# Connectors.net
KiCad netlist of a schematic drawn in Altium Designer
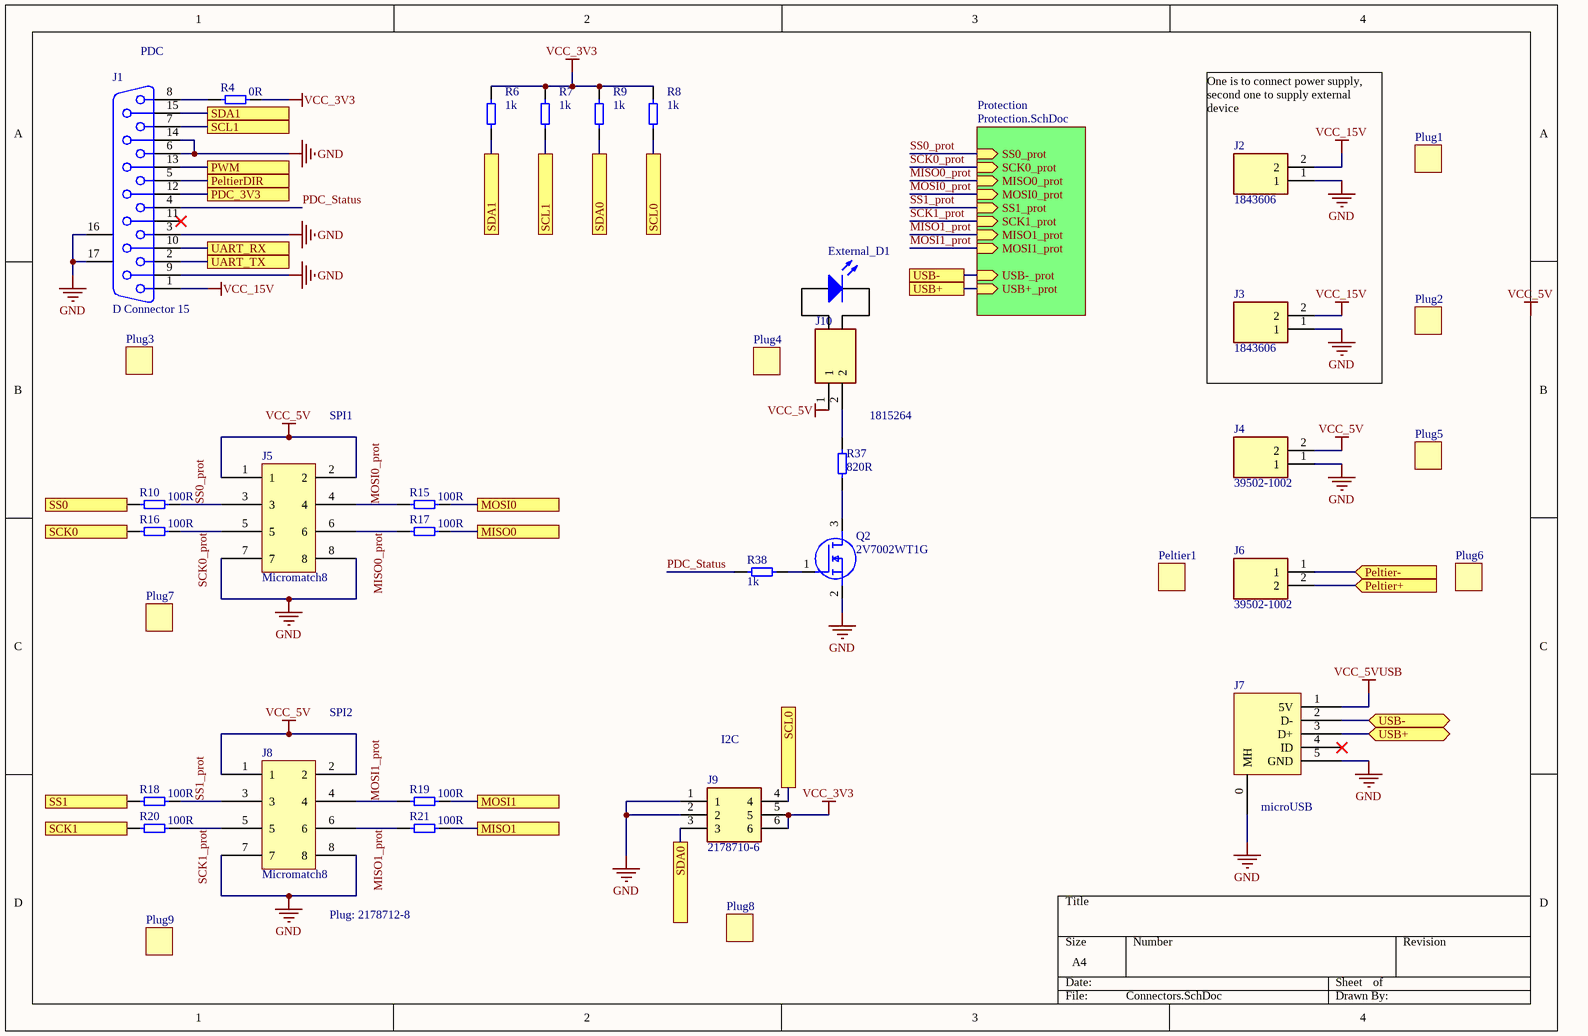
[diagram p0: Connectors.SchDoc]

(export (version "E")
  (design (tool "Eeschema 10.0.6"))
  (components
    (comp (ref "External_D1")
      (value "LED0")
      (description "External panel mounted LED")
      (fields (field (name "MANUFACTURER") "Dialight"))
      (libsource (lib "Miscellaneous Devices") (part "LED0"))
    )
    (comp (ref "J1")
      (value "D Connector 15")
      (footprint "DSUB_15_D15S33E4GV00LF")
      (description "Receptacle Assembly, 15 Position, Right Angle")
      (fields (field (name "MANUFACTURER") "Amphenol ICC") (field (name "PUBLISHER") "Altium Limited"))
      (libsource (lib "Miscellaneous Connectors") (part "D Connector 15"))
    )
    (comp (ref "J2")
      (value "1843606")
      (footprint "MouserDropbox:SHDR2W80P0X350_1X2_840X725X920P")
      (description "Connector")
      (fields (field (name "MOUSER PART NUMBER") "651-1843606") (field (name "RS PART NUMBER") "8042194"))
      (libsource (lib "*") (part "1843606"))
    )
    (comp (ref "J3")
      (value "1843606")
      (footprint "MouserDropbox:SHDR2W80P0X350_1X2_840X725X920P")
      (description "Connector")
      (fields (field (name "MOUSER PART NUMBER") "651-1843606") (field (name "RS PART NUMBER") "8042194"))
      (libsource (lib "*") (part "1843606"))
    )
    (comp (ref "J4")
      (value "39502-1002")
      (footprint "MouserDropbox:SHDR2W110P0X350_1X2_840X920X690P")
      (description "Connector")
      (fields (field (name "MOUSER PART NUMBER") "538-39502-1002"))
      (libsource (lib "*") (part "39502-1002"))
    )
    (comp (ref "J5")
      (value "Micromatch8")
      (footprint "micromatch8")
      (fields (field (name "MANUFACTURER") "TE Connectivity"))
      (libsource (lib "connectorsSymbols") (part "Micromatch8"))
    )
    (comp (ref "J6")
      (value "39502-1002")
      (footprint "MouserDropbox:SHDR2W110P0X350_1X2_840X920X690P")
      (description "Connector")
      (fields (field (name "MOUSER PART NUMBER") "538-39502-1002"))
      (libsource (lib "") (part "39502-1002_1"))
    )
    (comp (ref "J7")
      (value "microUSB")
      (footprint "microUSB_molex_476540001")
      (description "Molex 476540001")
      (fields (field (name "MANUFACTURER") "Molex"))
      (libsource (lib "connectorsSymbols") (part "microUSB_molex_476540001"))
    )
    (comp (ref "J8")
      (value "Micromatch8")
      (footprint "micromatch8")
      (fields (field (name "MANUFACTURER") "TE Connectivity"))
      (libsource (lib "connectorsSymbols") (part "Micromatch8"))
    )
    (comp (ref "J9")
      (value "2178710-6")
      (footprint "MouserDropbox:21787106")
      (description "Connector")
      (fields (field (name "MOUSER PART NUMBER") "571-2178710-6") (field (name "RS PART NUMBER") "8475468P"))
      (libsource (lib "*") (part "2178710-6"))
    )
    (comp (ref "J10")
      (value "1815264")
      (footprint "MouserDropbox:1815264")
      (description "Connector")
      (fields (field (name "MOUSER PART NUMBER") "651-1815264") (field (name "RS PART NUMBER") "8020138"))
      (libsource (lib "*") (part "1815264"))
    )
    (comp (ref "Peltier1")
      (value "plug")
      (fields (field (name "MANUFACTURER") "Laird Thermal Systems"))
      (libsource (lib "connectorsSymbols") (part "plug"))
    )
    (comp (ref "Plug1")
      (value "plug")
      (fields (field (name "MANUFACTURER") "Phoenix Contact"))
      (libsource (lib "connectorsSymbols") (part "plug"))
    )
    (comp (ref "Plug2")
      (value "plug")
      (fields (field (name "MANUFACTURER") "Phoenix Contact"))
      (libsource (lib "connectorsSymbols") (part "plug"))
    )
    (comp (ref "Plug3")
      (value "plug")
      (fields (field (name "MANUFACTURER") "Amphenol"))
      (libsource (lib "connectorsSymbols") (part "plug"))
    )
    (comp (ref "Plug4")
      (value "plug")
      (fields (field (name "MANUFACTURER") "Phoenix Contact"))
      (libsource (lib "connectorsSymbols") (part "plug"))
    )
    (comp (ref "Plug5")
      (value "plug")
      (fields (field (name "MANUFACTURER") "Molex"))
      (libsource (lib "connectorsSymbols") (part "plug"))
    )
    (comp (ref "Plug6")
      (value "plug")
      (fields (field (name "MANUFACTURER") "Molex"))
      (libsource (lib "connectorsSymbols") (part "plug"))
    )
    (comp (ref "Plug7")
      (value "plug")
      (fields (field (name "MANUFACTURER") "TE Connectivity"))
      (libsource (lib "connectorsSymbols") (part "plug"))
    )
    (comp (ref "Plug8")
      (value "plug")
      (fields (field (name "MANUFACTURER") "TE Connectivity"))
      (libsource (lib "connectorsSymbols") (part "plug"))
    )
    (comp (ref "Plug9")
      (value "plug")
      (fields (field (name "MANUFACTURER") "TE Connectivity"))
      (libsource (lib "connectorsSymbols") (part "plug"))
    )
    (comp (ref "Q2")
      (value "2V7002WT1G")
      (footprint "MouserDropbox:SOT65P220X100-3N")
      (description "MOSFET (N-Channel)")
      (fields (field (name "MOUSER PART NUMBER") "863-2V7002WT1G") (field (name "RS PART NUMBER") "7905246P"))
      (libsource (lib "*") (part "2V7002WT1G"))
    )
    (comp (ref "R4")
      (value "0R")
      (footprint "0603-Resistor")
      (description "Resistor")
      (fields (field (name "PART NUMBER") "R0603"))
      (libsource (lib "ZUIAM_LIB") (part "Resistor"))
    )
    (comp (ref "R6")
      (value "1k")
      (footprint "0603-Resistor")
      (description "Resistor")
      (fields (field (name "PART NUMBER") "R0603"))
      (libsource (lib "") (part "Resistor_1"))
    )
    (comp (ref "R7")
      (value "1k")
      (footprint "0603-Resistor")
      (description "Resistor")
      (fields (field (name "PART NUMBER") "R0603"))
      (libsource (lib "") (part "Resistor_1"))
    )
    (comp (ref "R8")
      (value "1k")
      (footprint "0603-Resistor")
      (description "Resistor")
      (fields (field (name "PART NUMBER") "R0603"))
      (libsource (lib "") (part "Resistor_1"))
    )
    (comp (ref "R9")
      (value "1k")
      (footprint "0603-Resistor")
      (description "Resistor")
      (fields (field (name "PART NUMBER") "R0603"))
      (libsource (lib "") (part "Resistor_1"))
    )
    (comp (ref "R10")
      (value "100R")
      (footprint "0603-Resistor")
      (description "Resistor")
      (fields (field (name "PART NUMBER") "R0603"))
      (libsource (lib "ZUIAM_LIB") (part "Resistor"))
    )
    (comp (ref "R15")
      (value "100R")
      (footprint "0603-Resistor")
      (description "Resistor")
      (fields (field (name "PART NUMBER") "R0603"))
      (libsource (lib "ZUIAM_LIB") (part "Resistor"))
    )
    (comp (ref "R16")
      (value "100R")
      (footprint "0603-Resistor")
      (description "Resistor")
      (fields (field (name "PART NUMBER") "R0603"))
      (libsource (lib "ZUIAM_LIB") (part "Resistor"))
    )
    (comp (ref "R17")
      (value "100R")
      (footprint "0603-Resistor")
      (description "Resistor")
      (fields (field (name "PART NUMBER") "R0603"))
      (libsource (lib "ZUIAM_LIB") (part "Resistor"))
    )
    (comp (ref "R18")
      (value "100R")
      (footprint "0603-Resistor")
      (description "Resistor")
      (fields (field (name "PART NUMBER") "R0603"))
      (libsource (lib "ZUIAM_LIB") (part "Resistor"))
    )
    (comp (ref "R19")
      (value "100R")
      (footprint "0603-Resistor")
      (description "Resistor")
      (fields (field (name "PART NUMBER") "R0603"))
      (libsource (lib "ZUIAM_LIB") (part "Resistor"))
    )
    (comp (ref "R20")
      (value "100R")
      (footprint "0603-Resistor")
      (description "Resistor")
      (fields (field (name "PART NUMBER") "R0603"))
      (libsource (lib "ZUIAM_LIB") (part "Resistor"))
    )
    (comp (ref "R21")
      (value "100R")
      (footprint "0603-Resistor")
      (description "Resistor")
      (fields (field (name "PART NUMBER") "R0603"))
      (libsource (lib "ZUIAM_LIB") (part "Resistor"))
    )
    (comp (ref "R37")
      (value "820R")
      (footprint "0603-Resistor")
      (description "Resistor")
      (fields (field (name "PART NUMBER") "R0603"))
      (libsource (lib "") (part "Resistor_2"))
    )
    (comp (ref "R38")
      (value "1k")
      (footprint "0603-Resistor")
      (description "Resistor")
      (fields (field (name "PART NUMBER") "R0603"))
      (libsource (lib "ZUIAM_LIB") (part "Resistor"))
    )
  )
  (nets
    (net (code "1") (name "/MISO0") (class "Default")
      (node (ref "R17") (pin "1") (pinfunction "1_1") (pintype "passive"))
    )
    (net (code "2") (name "/MISO0_prot") (class "Default")
      (node (ref "J5") (pin "6") (pinfunction "6_6") (pintype "passive"))
      (node (ref "R17") (pin "2") (pinfunction "2_2") (pintype "passive"))
    )
    (net (code "3") (name "/MISO1") (class "Default")
      (node (ref "R21") (pin "1") (pinfunction "1_1") (pintype "passive"))
    )
    (net (code "4") (name "/MISO1_prot") (class "Default")
      (node (ref "J8") (pin "6") (pinfunction "6_6") (pintype "passive"))
      (node (ref "R21") (pin "2") (pinfunction "2_2") (pintype "passive"))
    )
    (net (code "5") (name "/MOSI0") (class "Default")
      (node (ref "R15") (pin "1") (pinfunction "1_1") (pintype "passive"))
    )
    (net (code "6") (name "/MOSI0_prot") (class "Default")
      (node (ref "J5") (pin "4") (pinfunction "4_4") (pintype "passive"))
      (node (ref "R15") (pin "2") (pinfunction "2_2") (pintype "passive"))
    )
    (net (code "7") (name "/MOSI1") (class "Default")
      (node (ref "R19") (pin "1") (pinfunction "1_1") (pintype "passive"))
    )
    (net (code "8") (name "/MOSI1_prot") (class "Default")
      (node (ref "J8") (pin "4") (pinfunction "4_4") (pintype "passive"))
      (node (ref "R19") (pin "2") (pinfunction "2_2") (pintype "passive"))
    )
    (net (code "9") (name "/PDC_3V3") (class "Default")
      (node (ref "J1") (pin "12") (pinfunction "12_12") (pintype "passive"))
    )
    (net (code "10") (name "/PDC_Status") (class "Default")
      (node (ref "J1") (pin "4") (pinfunction "4_4") (pintype "passive"))
      (node (ref "R38") (pin "2") (pinfunction "2_2") (pintype "passive"))
    )
    (net (code "11") (name "/PWM") (class "Default")
      (node (ref "J1") (pin "13") (pinfunction "13_13") (pintype "passive"))
    )
    (net (code "12") (name "/Peltier+") (class "Default")
      (node (ref "J6") (pin "2") (pinfunction "2_2") (pintype "passive"))
    )
    (net (code "13") (name "/Peltier-") (class "Default")
      (node (ref "J6") (pin "1") (pinfunction "1_1") (pintype "passive"))
    )
    (net (code "14") (name "/PeltierDIR") (class "Default")
      (node (ref "J1") (pin "5") (pinfunction "5_5") (pintype "passive"))
    )
    (net (code "15") (name "/SCK0") (class "Default")
      (node (ref "R16") (pin "2") (pinfunction "2_2") (pintype "passive"))
    )
    (net (code "16") (name "/SCK0_prot") (class "Default")
      (node (ref "J5") (pin "5") (pinfunction "5_5") (pintype "passive"))
      (node (ref "R16") (pin "1") (pinfunction "1_1") (pintype "passive"))
    )
    (net (code "17") (name "/SCK1") (class "Default")
      (node (ref "R20") (pin "2") (pinfunction "2_2") (pintype "passive"))
    )
    (net (code "18") (name "/SCK1_prot") (class "Default")
      (node (ref "J8") (pin "5") (pinfunction "5_5") (pintype "passive"))
      (node (ref "R20") (pin "1") (pinfunction "1_1") (pintype "passive"))
    )
    (net (code "19") (name "/SCL0") (class "Default")
      (node (ref "J9") (pin "4") (pinfunction "4_4") (pintype "passive"))
      (node (ref "R8") (pin "1") (pinfunction "1_1") (pintype "passive"))
    )
    (net (code "20") (name "/SCL1") (class "Default")
      (node (ref "J1") (pin "7") (pinfunction "7_7") (pintype "passive"))
      (node (ref "R7") (pin "1") (pinfunction "1_1") (pintype "passive"))
    )
    (net (code "21") (name "/SDA0") (class "Default")
      (node (ref "J9") (pin "3") (pinfunction "3_3") (pintype "passive"))
      (node (ref "R9") (pin "1") (pinfunction "1_1") (pintype "passive"))
    )
    (net (code "22") (name "/SDA1") (class "Default")
      (node (ref "J1") (pin "15") (pinfunction "15_15") (pintype "passive"))
      (node (ref "R6") (pin "1") (pinfunction "1_1") (pintype "passive"))
    )
    (net (code "23") (name "/SS0") (class "Default")
      (node (ref "R10") (pin "2") (pinfunction "2_2") (pintype "passive"))
    )
    (net (code "24") (name "/SS0_prot") (class "Default")
      (node (ref "J5") (pin "3") (pinfunction "3_3") (pintype "passive"))
      (node (ref "R10") (pin "1") (pinfunction "1_1") (pintype "passive"))
    )
    (net (code "25") (name "/SS1") (class "Default")
      (node (ref "R18") (pin "2") (pinfunction "2_2") (pintype "passive"))
    )
    (net (code "26") (name "/SS1_prot") (class "Default")
      (node (ref "J8") (pin "3") (pinfunction "3_3") (pintype "passive"))
      (node (ref "R18") (pin "1") (pinfunction "1_1") (pintype "passive"))
    )
    (net (code "27") (name "/UART_RX") (class "Default")
      (node (ref "J1") (pin "10") (pinfunction "10_10") (pintype "passive"))
    )
    (net (code "28") (name "/UART_TX") (class "Default")
      (node (ref "J1") (pin "2") (pinfunction "2_2") (pintype "passive"))
    )
    (net (code "29") (name "/USB+") (class "Default")
      (node (ref "J7") (pin "3") (pinfunction "D+_3") (pintype "passive"))
    )
    (net (code "30") (name "/USB-") (class "Default")
      (node (ref "J7") (pin "2") (pinfunction "D-_2") (pintype "passive"))
    )
    (net (code "31") (name "GND") (class "Default")
      (node (ref "J1") (pin "14") (pinfunction "14_14") (pintype "passive"))
      (node (ref "J1") (pin "16") (pinfunction "MH1_16") (pintype "passive"))
      (node (ref "J1") (pin "17") (pinfunction "MH2_17") (pintype "passive"))
      (node (ref "J1") (pin "3") (pinfunction "3_3") (pintype "passive"))
      (node (ref "J1") (pin "6") (pinfunction "6_6") (pintype "passive"))
      (node (ref "J1") (pin "9") (pinfunction "9_9") (pintype "passive"))
      (node (ref "J2") (pin "1") (pinfunction "1_1") (pintype "passive"))
      (node (ref "J3") (pin "1") (pinfunction "1_1") (pintype "passive"))
      (node (ref "J4") (pin "1") (pinfunction "1_1") (pintype "passive"))
      (node (ref "J5") (pin "7") (pinfunction "7_7") (pintype "passive"))
      (node (ref "J5") (pin "8") (pinfunction "8_8") (pintype "passive"))
      (node (ref "J7") (pin "0") (pinfunction "MH_0") (pintype "passive"))
      (node (ref "J7") (pin "5") (pinfunction "GND_5") (pintype "passive"))
      (node (ref "J8") (pin "7") (pinfunction "7_7") (pintype "passive"))
      (node (ref "J8") (pin "8") (pinfunction "8_8") (pintype "passive"))
      (node (ref "J9") (pin "1") (pinfunction "1_1") (pintype "passive"))
      (node (ref "J9") (pin "2") (pinfunction "2_2") (pintype "passive"))
      (node (ref "Q2") (pin "2") (pinfunction "S_2") (pintype "passive"))
    )
    (net (code "32") (name "Net-(J1-Pad8)") (class "Default")
      (node (ref "J1") (pin "8") (pinfunction "8_8") (pintype "passive"))
      (node (ref "R4") (pin "2") (pinfunction "2_2") (pintype "passive"))
    )
    (net (code "33") (name "Net-(J10-Pad2)") (class "Default")
      (node (ref "J10") (pin "2") (pinfunction "2_2") (pintype "passive"))
      (node (ref "R37") (pin "1") (pinfunction "1_1") (pintype "passive"))
    )
    (net (code "34") (name "Net-(Q2-D)") (class "Default")
      (node (ref "Q2") (pin "3") (pinfunction "D_3") (pintype "passive"))
      (node (ref "R37") (pin "2") (pinfunction "2_2") (pintype "passive"))
    )
    (net (code "35") (name "Net-(Q2-G)") (class "Default")
      (node (ref "Q2") (pin "1") (pinfunction "G_1") (pintype "passive"))
      (node (ref "R38") (pin "1") (pinfunction "1_1") (pintype "passive"))
    )
    (net (code "36") (name "VCC_3V3") (class "Default")
      (node (ref "J9") (pin "5") (pinfunction "5_5") (pintype "passive"))
      (node (ref "J9") (pin "6") (pinfunction "6_6") (pintype "passive"))
      (node (ref "R4") (pin "1") (pinfunction "1_1") (pintype "passive"))
      (node (ref "R6") (pin "2") (pinfunction "2_2") (pintype "passive"))
      (node (ref "R7") (pin "2") (pinfunction "2_2") (pintype "passive"))
      (node (ref "R8") (pin "2") (pinfunction "2_2") (pintype "passive"))
      (node (ref "R9") (pin "2") (pinfunction "2_2") (pintype "passive"))
    )
    (net (code "37") (name "VCC_5V") (class "Default")
      (node (ref "J10") (pin "1") (pinfunction "1_1") (pintype "passive"))
      (node (ref "J4") (pin "2") (pinfunction "2_2") (pintype "passive"))
      (node (ref "J5") (pin "1") (pinfunction "1_1") (pintype "passive"))
      (node (ref "J5") (pin "2") (pinfunction "2_2") (pintype "passive"))
      (node (ref "J8") (pin "1") (pinfunction "1_1") (pintype "passive"))
      (node (ref "J8") (pin "2") (pinfunction "2_2") (pintype "passive"))
    )
    (net (code "38") (name "VCC_5VUSB") (class "Default")
      (node (ref "J7") (pin "1") (pinfunction "5V_1") (pintype "passive"))
    )
    (net (code "39") (name "VCC_15V") (class "Default")
      (node (ref "J1") (pin "1") (pinfunction "1_1") (pintype "passive"))
      (node (ref "J2") (pin "2") (pinfunction "2_2") (pintype "passive"))
      (node (ref "J3") (pin "2") (pinfunction "2_2") (pintype "passive"))
    )
    (net (code "40") (name "unconnected-(External_D1-A-Pad1)") (class "Default")
      (node (ref "External_D1") (pin "1") (pinfunction "A_1") (pintype "passive"))
    )
    (net (code "41") (name "unconnected-(External_D1-K-Pad2)") (class "Default")
      (node (ref "External_D1") (pin "2") (pinfunction "K_2") (pintype "passive"))
    )
    (net (code "42") (name "unconnected-(J1-Pad11)") (class "Default")
      (node (ref "J1") (pin "11") (pinfunction "11_11") (pintype "passive+no_connect"))
    )
    (net (code "43") (name "unconnected-(J7-ID-Pad4)") (class "Default")
      (node (ref "J7") (pin "4") (pinfunction "ID_4") (pintype "passive+no_connect"))
    )
  )
)
